# HM-MYS_relay_board_v1_0.net
KiCad netlist of a schematic drawn in EAGLE
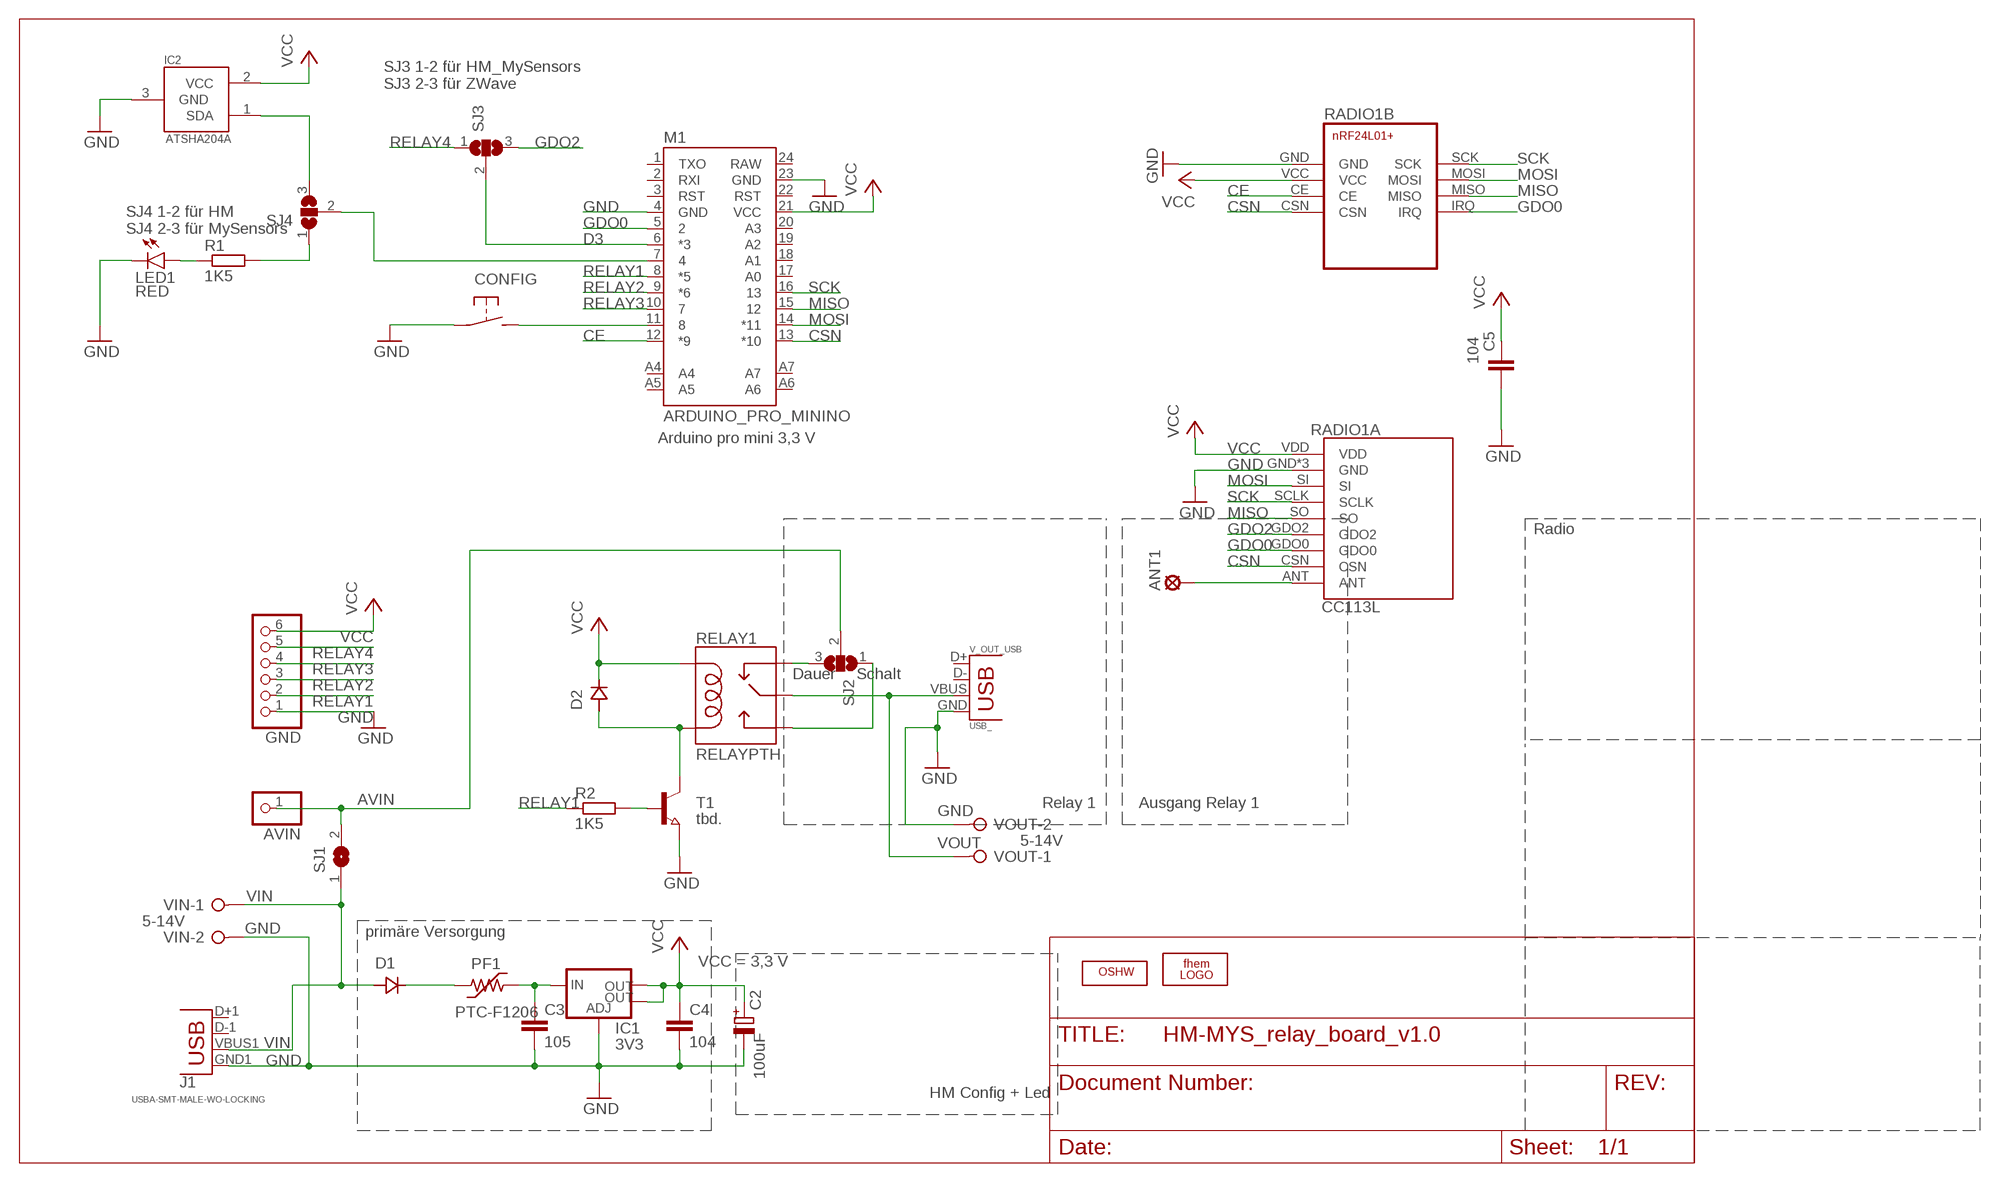
[diagram p0: schematic, sheet 1]

(export (version "E")
  (design (tool "Eeschema 10.0.6"))
  (components
    (comp (ref "ANT1")
      (value "LSP10")
      (footprint "eagle-import:LSP10")
      (libsource (lib "eagle-import") (part "LSP10"))
    )
    (comp (ref "AVIN")
      (value "PINHD-1X1")
      (footprint "eagle-import:1X01")
      (libsource (lib "eagle-import") (part "PINHD-1X1"))
    )
    (comp (ref "C2")
      (value "100uF")
      (footprint "eagle-import:E2,5-6E")
      (libsource (lib "eagle-import") (part "CPOL-EUE2,5-6E"))
    )
    (comp (ref "C3")
      (value "105")
      (footprint "eagle-import:C0805")
      (libsource (lib "eagle-import") (part "C-EUC0805"))
    )
    (comp (ref "C4")
      (value "104")
      (footprint "eagle-import:C0805")
      (libsource (lib "eagle-import") (part "C-EUC0805"))
    )
    (comp (ref "C5")
      (value "104")
      (footprint "eagle-import:C0805")
      (libsource (lib "eagle-import") (part "C-EUC0805"))
    )
    (comp (ref "CONFIG")
      (value "TASTERSMD")
      (footprint "eagle-import:TASTER-SMD")
      (libsource (lib "eagle-import") (part "TASTERSMD"))
    )
    (comp (ref "D1")
      (value "SS14")
      (footprint "eagle-import:DO214")
      (libsource (lib "eagle-import") (part "SS14"))
    )
    (comp (ref "D2")
      (value "SS14")
      (footprint "eagle-import:DO214")
      (libsource (lib "eagle-import") (part "SS14"))
    )
    (comp (ref "GND")
      (value "PINHD-1X6_S")
      (footprint "eagle-import:1X06")
      (libsource (lib "eagle-import") (part "PINHD-1X6_S"))
    )
    (comp (ref "IC1")
      (value "3V3")
      (footprint "eagle-import:SOT223")
      (libsource (lib "eagle-import") (part "V_REG_LM1117SOT223"))
    )
    (comp (ref "IC2")
      (value "ATSHA204A")
      (footprint "eagle-import:SOT23-3")
      (libsource (lib "eagle-import") (part "IC_ATSHA204A_CRYPT"))
    )
    (comp (ref "J1")
      (value "USBA-SMT-MALE-WO-LOCKING")
      (footprint "eagle-import:USB-A-SMT-MALE-NO_LOCKING")
      (libsource (lib "eagle-import") (part "USBA-SMT-MALE-WO-LOCKING"))
    )
    (comp (ref "LED1")
      (value "RED")
      (footprint "eagle-import:LED-1206")
      (libsource (lib "eagle-import") (part "LED-RED1206"))
    )
    (comp (ref "LOGO2")
      (value "LOGO_OSHWX0070")
      (footprint "eagle-import:OSHW_6X70")
      (libsource (lib "eagle-import") (part "LOGO_OSHWX0070"))
    )
    (comp (ref "M1")
      (value "ARDUINO_PRO_MININO")
      (footprint "eagle-import:ARDUINO_PRO_MINI_O")
      (libsource (lib "eagle-import") (part "ARDUINO_PRO_MININO"))
    )
    (comp (ref "PF1")
      (value "PTC-F1206")
      (footprint "eagle-import:F1206")
      (libsource (lib "eagle-import") (part "PTC-F1206"))
    )
    (comp (ref "R1")
      (value "1K5")
      (footprint "eagle-import:R0805_SMALL_GAP")
      (libsource (lib "eagle-import") (part "R0805_SMALL_GAP"))
    )
    (comp (ref "R2")
      (value "1K5")
      (footprint "eagle-import:R0805_SMALL_GAP")
      (libsource (lib "eagle-import") (part "R0805_SMALL_GAP"))
    )
    (comp (ref "RADIO1A")
      (value "CC113L")
      (footprint "eagle-import:CC113L")
      (libsource (lib "eagle-import") (part "CC113L"))
    )
    (comp (ref "RADIO1B")
      (value "NRF24L01+NRF24L01+MINI")
      (footprint "eagle-import:NRF24L01+MINI")
      (libsource (lib "eagle-import") (part "NRF24L01+NRF24L01+MINI"))
    )
    (comp (ref "RELAY1")
      (value "RELAYPTH")
      (footprint "eagle-import:SRD-05VDC-SL-C")
      (libsource (lib "eagle-import") (part "RELAYPTH"))
    )
    (comp (ref "SJ1") (value "SJ") (footprint "eagle-import:SJ") (libsource (lib "eagle-import") (part "SJ")))
    (comp (ref "SJ2")
      (value "SJ2W")
      (footprint "eagle-import:SJ_2")
      (libsource (lib "eagle-import") (part "SJ2W"))
    )
    (comp (ref "SJ3")
      (value "SJ2W")
      (footprint "eagle-import:SJ_2")
      (libsource (lib "eagle-import") (part "SJ2W"))
    )
    (comp (ref "SJ4")
      (value "SJ2W")
      (footprint "eagle-import:SJ_2")
      (libsource (lib "eagle-import") (part "SJ2W"))
    )
    (comp (ref "T1")
      (value "tbd.")
      (footprint "eagle-import:SOT89")
      (libsource (lib "eagle-import") (part "NPN-TRANSISTOR_SOT89"))
    )
    (comp (ref "U$2")
      (value "LOGO_FHEMSTOP")
      (footprint "eagle-import:LOGO_FHEM_3X3_STOP")
      (libsource (lib "eagle-import") (part "LOGO_FHEMSTOP"))
    )
    (comp (ref "VIN")
      (value "W237-02P")
      (footprint "eagle-import:W237-132")
      (libsource (lib "eagle-import") (part "W237-02P"))
    )
    (comp (ref "VOUT")
      (value "W237-02P")
      (footprint "eagle-import:W237-132")
      (libsource (lib "eagle-import") (part "W237-02P"))
    )
    (comp (ref "V_OUT_USB")
      (value "USB_")
      (footprint "eagle-import:USB-A-S-SILK-FEMALE")
      (libsource (lib "eagle-import") (part "USB_"))
    )
  )
  (nets
    (net (code "1") (name "/AVIN") (class "Default")
      (node (ref "AVIN") (pin "1") (pinfunction "1_1") (pintype "passive"))
      (node (ref "SJ1") (pin "2") (pinfunction "2_2") (pintype "passive"))
      (node (ref "SJ2") (pin "2") (pinfunction "2_2") (pintype "passive"))
    )
    (net (code "2") (name "/CE") (class "Default")
      (node (ref "M1") (pin "12") (pinfunction "*9_12") (pintype "bidirectional"))
      (node (ref "RADIO1B") (pin "CE") (pinfunction "CE_CE") (pintype "bidirectional"))
    )
    (net (code "3") (name "/CSN") (class "Default")
      (node (ref "M1") (pin "13") (pinfunction "*10_13") (pintype "bidirectional"))
      (node (ref "RADIO1A") (pin "CSN") (pinfunction "CSN_CSN") (pintype "bidirectional"))
      (node (ref "RADIO1B") (pin "CSN") (pinfunction "CSN_CSN") (pintype "bidirectional"))
    )
    (net (code "4") (name "/D3") (class "Default")
      (node (ref "M1") (pin "6") (pinfunction "*3_6") (pintype "bidirectional"))
      (node (ref "SJ3") (pin "2") (pinfunction "2_2") (pintype "passive"))
    )
    (net (code "5") (name "/GDO0") (class "Default")
      (node (ref "M1") (pin "5") (pinfunction "2_5") (pintype "bidirectional"))
      (node (ref "RADIO1A") (pin "GDO0") (pinfunction "GDO0_GDO0") (pintype "bidirectional"))
      (node (ref "RADIO1B") (pin "IRQ") (pinfunction "IRQ_IRQ") (pintype "bidirectional"))
    )
    (net (code "6") (name "/GDO2") (class "Default")
      (node (ref "RADIO1A") (pin "GDO2") (pinfunction "GDO2_GDO2") (pintype "bidirectional"))
      (node (ref "SJ3") (pin "3") (pinfunction "3_3") (pintype "passive"))
    )
    (net (code "7") (name "/MISO") (class "Default")
      (node (ref "M1") (pin "15") (pinfunction "12_15") (pintype "bidirectional"))
      (node (ref "RADIO1A") (pin "SO") (pinfunction "SO_SO") (pintype "bidirectional"))
      (node (ref "RADIO1B") (pin "MISO") (pinfunction "MISO_MISO") (pintype "bidirectional"))
    )
    (net (code "8") (name "/MOSI") (class "Default")
      (node (ref "M1") (pin "14") (pinfunction "*11_14") (pintype "bidirectional"))
      (node (ref "RADIO1A") (pin "SI") (pinfunction "SI_SI") (pintype "bidirectional"))
      (node (ref "RADIO1B") (pin "MOSI") (pinfunction "MOSI_MOSI") (pintype "bidirectional"))
    )
    (net (code "9") (name "/RELAY1") (class "Default")
      (node (ref "GND") (pin "2") (pinfunction "2_2") (pintype "passive"))
      (node (ref "M1") (pin "8") (pinfunction "*5_8") (pintype "bidirectional"))
      (node (ref "R2") (pin "1") (pinfunction "1_1") (pintype "passive"))
    )
    (net (code "10") (name "/RELAY2") (class "Default")
      (node (ref "GND") (pin "3") (pinfunction "3_3") (pintype "passive"))
      (node (ref "M1") (pin "9") (pinfunction "*6_9") (pintype "bidirectional"))
    )
    (net (code "11") (name "/RELAY3") (class "Default")
      (node (ref "GND") (pin "4") (pinfunction "4_4") (pintype "passive"))
      (node (ref "M1") (pin "10") (pinfunction "7_10") (pintype "bidirectional"))
    )
    (net (code "12") (name "/RELAY4") (class "Default")
      (node (ref "GND") (pin "5") (pinfunction "5_5") (pintype "passive"))
      (node (ref "SJ3") (pin "1") (pinfunction "1_1") (pintype "passive"))
    )
    (net (code "13") (name "/SCK") (class "Default")
      (node (ref "M1") (pin "16") (pinfunction "13_16") (pintype "bidirectional"))
      (node (ref "RADIO1A") (pin "SCLK") (pinfunction "SCLK_SCLK") (pintype "bidirectional"))
      (node (ref "RADIO1B") (pin "SCK") (pinfunction "SCK_SCK") (pintype "bidirectional"))
    )
    (net (code "14") (name "/VIN") (class "Default")
      (node (ref "D1") (pin "ANODE") (pinfunction "ANODE_ANODE") (pintype "bidirectional"))
      (node (ref "J1") (pin "VBUS1") (pinfunction "VBUS_VBUS1") (pintype "bidirectional"))
      (node (ref "SJ1") (pin "1") (pinfunction "1_1") (pintype "passive"))
      (node (ref "VIN") (pin "1") (pinfunction "KL_1") (pintype "passive"))
    )
    (net (code "15") (name "/VOUT") (class "Default")
      (node (ref "RELAY1") (pin "SWCOMMON") (pinfunction "SWCOMMON_SWCOMMON") (pintype "bidirectional"))
      (node (ref "VOUT") (pin "1") (pinfunction "KL_1") (pintype "passive"))
      (node (ref "V_OUT_USB") (pin "VBUS") (pinfunction "VBUS_VBUS") (pintype "bidirectional"))
    )
    (net (code "16") (name "GND") (class "Default")
      (node (ref "C2") (pin "-") (pinfunction "-_-") (pintype "passive"))
      (node (ref "C3") (pin "2") (pinfunction "2_2") (pintype "passive"))
      (node (ref "C4") (pin "2") (pinfunction "2_2") (pintype "passive"))
      (node (ref "C5") (pin "2") (pinfunction "2_2") (pintype "passive"))
      (node (ref "CONFIG") (pin "1") (pinfunction "P_1") (pintype "passive"))
      (node (ref "GND") (pin "1") (pinfunction "1_1") (pintype "passive"))
      (node (ref "IC1") (pin "1") (pinfunction "ADJ_1") (pintype "power_in"))
      (node (ref "IC2") (pin "3") (pinfunction "GND_3") (pintype "bidirectional"))
      (node (ref "J1") (pin "GND1") (pinfunction "GND_GND1") (pintype "bidirectional"))
      (node (ref "LED1") (pin "C") (pinfunction "C_C") (pintype "passive"))
      (node (ref "M1") (pin "23") (pinfunction "GND_23") (pintype "bidirectional"))
      (node (ref "M1") (pin "4") (pinfunction "GND_4") (pintype "bidirectional"))
      (node (ref "RADIO1A") (pin "GND") (pinfunction "GND_GND") (pintype "power_in"))
      (node (ref "RADIO1A") (pin "GND1") (pinfunction "GND_GND1") (pintype "power_in"))
      (node (ref "RADIO1A") (pin "GND2") (pinfunction "GND_GND2") (pintype "power_in"))
      (node (ref "RADIO1B") (pin "GND") (pinfunction "GND_GND") (pintype "power_in"))
      (node (ref "T1") (pin "3") (pinfunction "E_3") (pintype "passive"))
      (node (ref "VIN") (pin "2") (pinfunction "KL_2") (pintype "passive"))
      (node (ref "VOUT") (pin "2") (pinfunction "KL_2") (pintype "passive"))
      (node (ref "V_OUT_USB") (pin "GND") (pinfunction "GND_GND") (pintype "bidirectional"))
    )
    (net (code "17") (name "Net-(ANT1-MP)") (class "Default")
      (node (ref "ANT1") (pin "1") (pinfunction "MP_1") (pintype "passive"))
      (node (ref "RADIO1A") (pin "ANT") (pinfunction "ANT_ANT") (pintype "bidirectional"))
    )
    (net (code "18") (name "Net-(CONFIG-S)") (class "Default")
      (node (ref "CONFIG") (pin "2") (pinfunction "S_2") (pintype "passive"))
      (node (ref "M1") (pin "11") (pinfunction "8_11") (pintype "bidirectional"))
    )
    (net (code "19") (name "Net-(D1-PadCATHODE)") (class "Default")
      (node (ref "D1") (pin "CATHODE") (pinfunction "CATHODE_CATHODE") (pintype "bidirectional"))
      (node (ref "PF1") (pin "1") (pinfunction "1_1") (pintype "passive"))
    )
    (net (code "20") (name "Net-(IC1-IN)") (class "Default")
      (node (ref "C3") (pin "1") (pinfunction "1_1") (pintype "passive"))
      (node (ref "IC1") (pin "3") (pinfunction "IN_3") (pintype "power_in"))
      (node (ref "PF1") (pin "2") (pinfunction "2_2") (pintype "passive"))
    )
    (net (code "21") (name "Net-(IC2-SDA)") (class "Default")
      (node (ref "IC2") (pin "1") (pinfunction "SDA_1") (pintype "bidirectional"))
      (node (ref "SJ4") (pin "3") (pinfunction "3_3") (pintype "passive"))
    )
    (net (code "22") (name "Net-(LED1-PadA)") (class "Default")
      (node (ref "LED1") (pin "A") (pinfunction "A_A") (pintype "passive"))
      (node (ref "R1") (pin "1") (pinfunction "1_1") (pintype "passive"))
    )
    (net (code "23") (name "Net-(M1-4)") (class "Default")
      (node (ref "M1") (pin "7") (pinfunction "4_7") (pintype "bidirectional"))
      (node (ref "SJ4") (pin "2") (pinfunction "2_2") (pintype "passive"))
    )
    (net (code "24") (name "Net-(R1-Pad2)") (class "Default")
      (node (ref "R1") (pin "2") (pinfunction "2_2") (pintype "passive"))
      (node (ref "SJ4") (pin "1") (pinfunction "1_1") (pintype "passive"))
    )
    (net (code "25") (name "Net-(RELAY1-PadSWOPEN)") (class "Default")
      (node (ref "RELAY1") (pin "SWOPEN") (pinfunction "SWOPEN_SWOPEN") (pintype "bidirectional"))
      (node (ref "SJ2") (pin "1") (pinfunction "1_1") (pintype "passive"))
    )
    (net (code "26") (name "Net-(RELAY1-SWCLOSE)") (class "Default")
      (node (ref "RELAY1") (pin "SWCLOSED") (pinfunction "SWCLOSE_SWCLOSED") (pintype "bidirectional"))
      (node (ref "SJ2") (pin "3") (pinfunction "3_3") (pintype "passive"))
    )
    (net (code "27") (name "Net-(T1-B)") (class "Default")
      (node (ref "R2") (pin "2") (pinfunction "2_2") (pintype "passive"))
      (node (ref "T1") (pin "1") (pinfunction "B_1") (pintype "passive"))
    )
    (net (code "28") (name "Net-(T1-C)") (class "Default")
      (node (ref "D2") (pin "ANODE") (pinfunction "ANODE_ANODE") (pintype "bidirectional"))
      (node (ref "RELAY1") (pin "COIL0") (pinfunction "COIL0_COIL0") (pintype "bidirectional"))
      (node (ref "T1") (pin "2") (pinfunction "C_2") (pintype "passive"))
    )
    (net (code "29") (name "VCC") (class "Default")
      (node (ref "C2") (pin "+") (pinfunction "+_+") (pintype "passive"))
      (node (ref "C4") (pin "1") (pinfunction "1_1") (pintype "passive"))
      (node (ref "C5") (pin "1") (pinfunction "1_1") (pintype "passive"))
      (node (ref "D2") (pin "CATHODE") (pinfunction "CATHODE_CATHODE") (pintype "bidirectional"))
      (node (ref "GND") (pin "6") (pinfunction "6_6") (pintype "passive"))
      (node (ref "IC1") (pin "2") (pinfunction "OUT_2") (pintype "power_in"))
      (node (ref "IC1") (pin "4") (pinfunction "OUT_4") (pintype "power_in"))
      (node (ref "IC2") (pin "2") (pinfunction "VCC_2") (pintype "bidirectional"))
      (node (ref "M1") (pin "21") (pinfunction "VCC_21") (pintype "bidirectional"))
      (node (ref "RADIO1A") (pin "VDD") (pinfunction "VDD_VDD") (pintype "power_in"))
      (node (ref "RADIO1B") (pin "VCC") (pinfunction "VCC_VCC") (pintype "power_in"))
      (node (ref "RELAY1") (pin "COIL1") (pinfunction "COIL1_COIL1") (pintype "bidirectional"))
    )
    (net (code "30") (name "unconnected-(J1-D+-PadD+1)") (class "Default")
      (node (ref "J1") (pin "D+1") (pinfunction "D+_D+1") (pintype "bidirectional"))
    )
    (net (code "31") (name "unconnected-(J1-D--PadD-1)") (class "Default")
      (node (ref "J1") (pin "D-1") (pinfunction "D-_D-1") (pintype "bidirectional"))
    )
    (net (code "32") (name "unconnected-(M1-A0-Pad17)") (class "Default")
      (node (ref "M1") (pin "17") (pinfunction "A0_17") (pintype "bidirectional"))
    )
    (net (code "33") (name "unconnected-(M1-A1-Pad18)") (class "Default")
      (node (ref "M1") (pin "18") (pinfunction "A1_18") (pintype "bidirectional"))
    )
    (net (code "34") (name "unconnected-(M1-A2-Pad19)") (class "Default")
      (node (ref "M1") (pin "19") (pinfunction "A2_19") (pintype "bidirectional"))
    )
    (net (code "35") (name "unconnected-(M1-A3-Pad20)") (class "Default")
      (node (ref "M1") (pin "20") (pinfunction "A3_20") (pintype "bidirectional"))
    )
    (net (code "36") (name "unconnected-(M1-PadA4)") (class "Default")
      (node (ref "M1") (pin "A4") (pinfunction "A4_A4") (pintype "bidirectional"))
    )
    (net (code "37") (name "unconnected-(M1-PadA5)") (class "Default")
      (node (ref "M1") (pin "A5") (pinfunction "A5_A5") (pintype "bidirectional"))
    )
    (net (code "38") (name "unconnected-(M1-PadA6)") (class "Default")
      (node (ref "M1") (pin "A6") (pinfunction "A6_A6") (pintype "bidirectional"))
    )
    (net (code "39") (name "unconnected-(M1-PadA7)") (class "Default")
      (node (ref "M1") (pin "A7") (pinfunction "A7_A7") (pintype "bidirectional"))
    )
    (net (code "40") (name "unconnected-(M1-RAW-Pad24)") (class "Default")
      (node (ref "M1") (pin "24") (pinfunction "RAW_24") (pintype "bidirectional"))
    )
    (net (code "41") (name "unconnected-(M1-RST-Pad3)") (class "Default")
      (node (ref "M1") (pin "3") (pinfunction "RST_3") (pintype "bidirectional"))
    )
    (net (code "42") (name "unconnected-(M1-RST-Pad22)") (class "Default")
      (node (ref "M1") (pin "22") (pinfunction "RST_22") (pintype "bidirectional"))
    )
    (net (code "43") (name "unconnected-(M1-RXI-Pad2)") (class "Default")
      (node (ref "M1") (pin "2") (pinfunction "RXI_2") (pintype "bidirectional"))
    )
    (net (code "44") (name "unconnected-(M1-TXO-Pad1)") (class "Default")
      (node (ref "M1") (pin "1") (pinfunction "TXO_1") (pintype "bidirectional"))
    )
    (net (code "45") (name "unconnected-(V_OUT_USB-PadD+)") (class "Default")
      (node (ref "V_OUT_USB") (pin "D+") (pinfunction "D+_D+") (pintype "bidirectional"))
    )
    (net (code "46") (name "unconnected-(V_OUT_USB-PadD-)") (class "Default")
      (node (ref "V_OUT_USB") (pin "D-") (pinfunction "D-_D-") (pintype "bidirectional"))
    )
  )
)
